# The_Yowler_v9.net
KiCad netlist of a schematic drawn in EAGLE
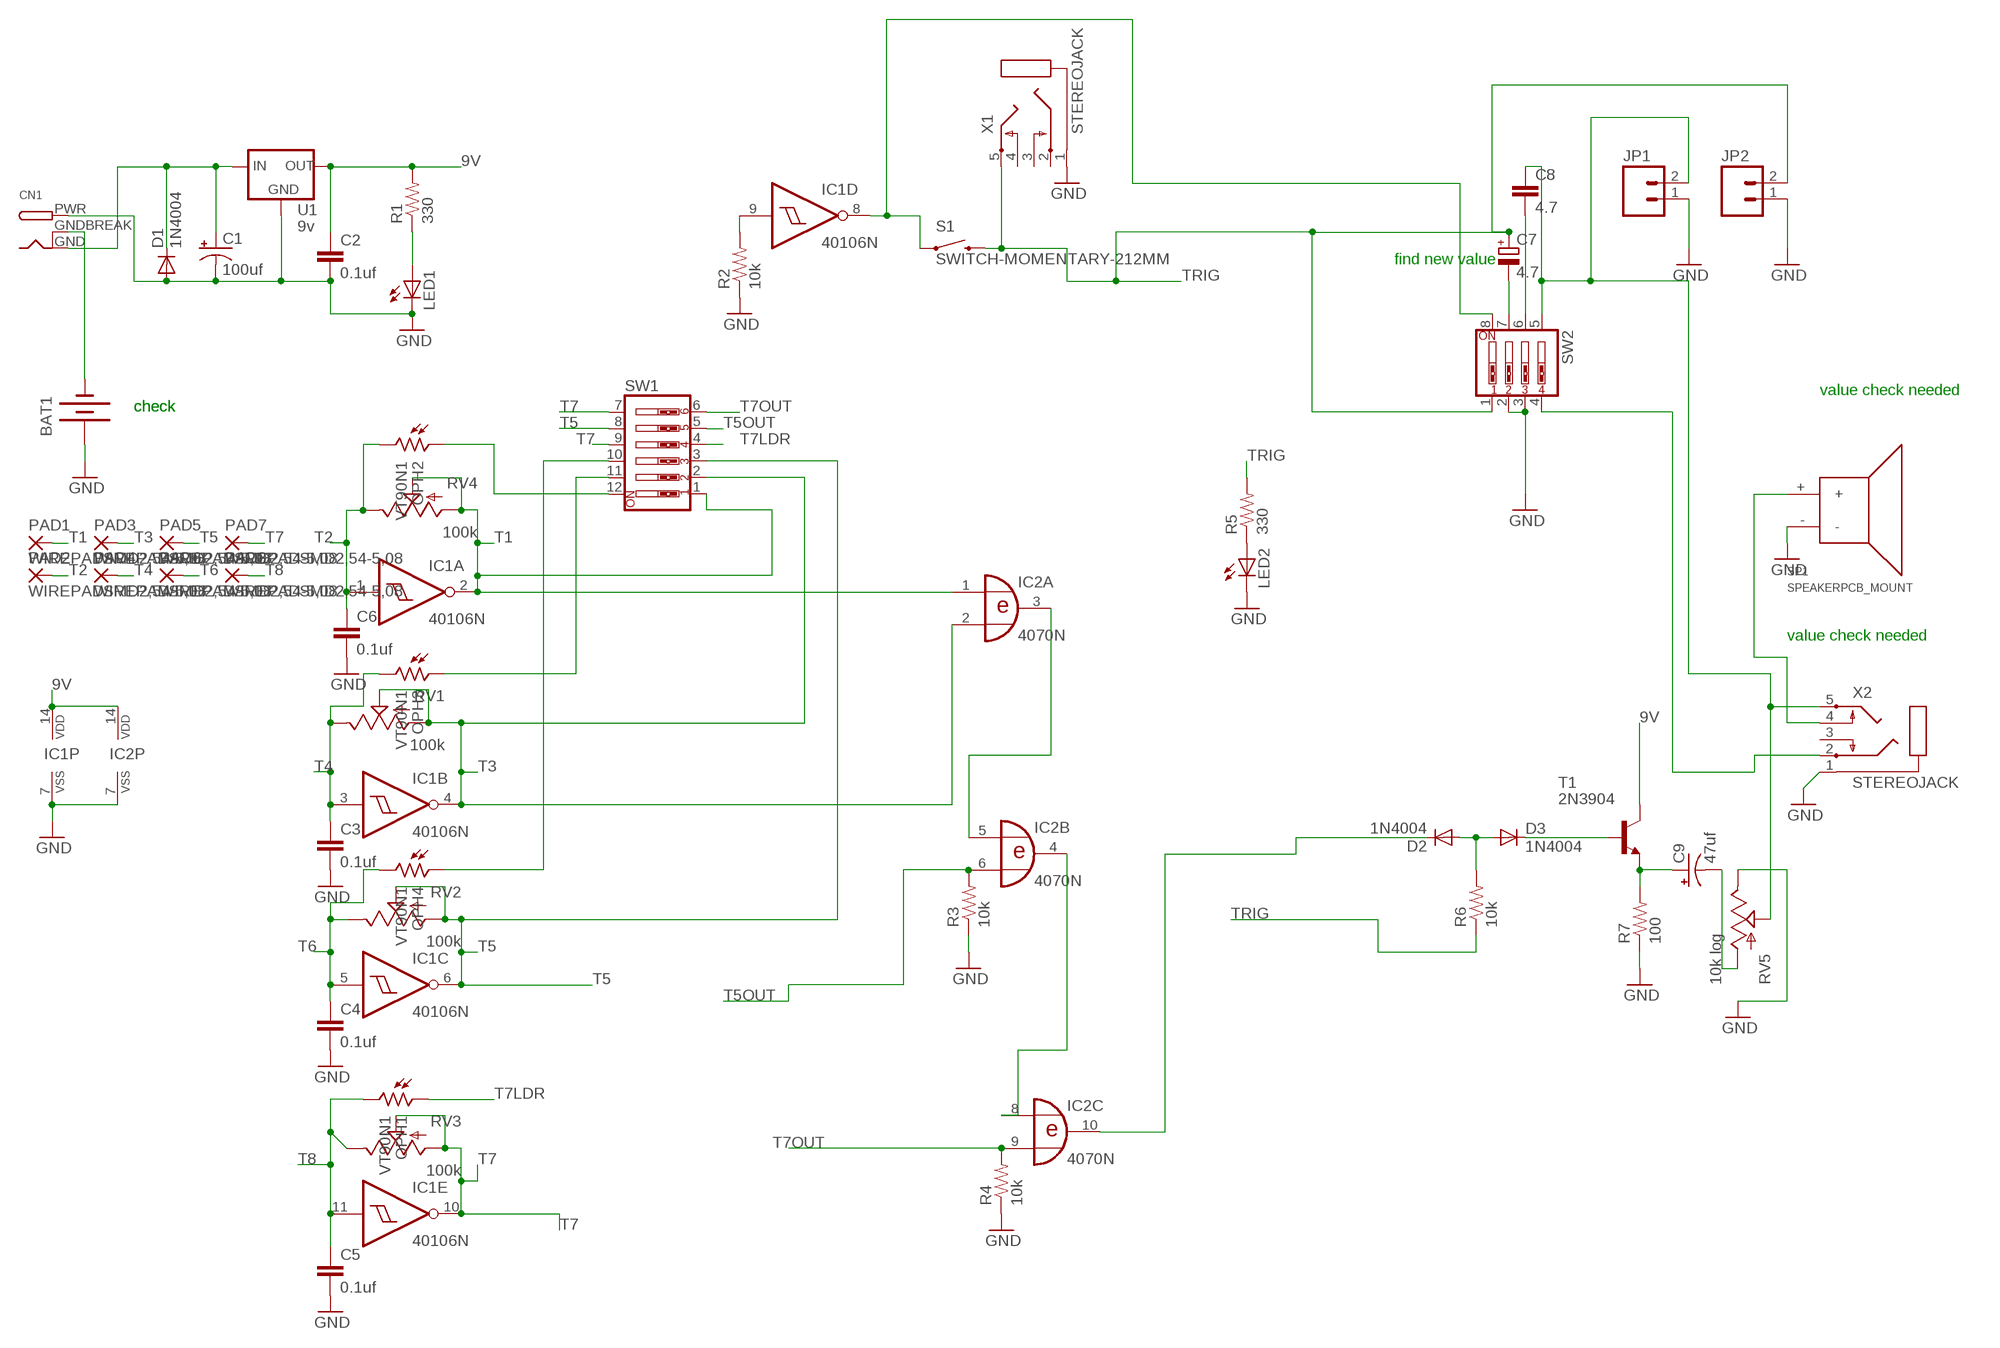
[diagram p0: schematic, sheet 1]

(export (version "E")
  (design (tool "Eeschema 10.0.6"))
  (components
    (comp (ref "BAT1")
      (value "BATTERY9V")
      (footprint "eagle-import:BATTCON_9V")
      (libsource (lib "eagle-import") (part "BATTERY9V"))
    )
    (comp (ref "C1")
      (value "100uf")
      (footprint "eagle-import:E5-6")
      (libsource (lib "eagle-import") (part "CPOL-USE5-6"))
    )
    (comp (ref "C2")
      (value "0.1uf")
      (footprint "eagle-import:CAP-PTH-5MM")
      (libsource (lib "eagle-import") (part "CAPPTH1"))
    )
    (comp (ref "C3")
      (value "0.1uf")
      (footprint "eagle-import:CAP-PTH-5MM")
      (libsource (lib "eagle-import") (part "CAPPTH1"))
    )
    (comp (ref "C4")
      (value "0.1uf")
      (footprint "eagle-import:CAP-PTH-5MM")
      (libsource (lib "eagle-import") (part "CAPPTH1"))
    )
    (comp (ref "C5")
      (value "0.1uf")
      (footprint "eagle-import:CAP-PTH-5MM")
      (libsource (lib "eagle-import") (part "CAPPTH1"))
    )
    (comp (ref "C6")
      (value "0.1uf")
      (footprint "eagle-import:CAP-PTH-5MM")
      (libsource (lib "eagle-import") (part "CAPPTH1"))
    )
    (comp (ref "C7")
      (value "4.7")
      (footprint "eagle-import:E5-5")
      (libsource (lib "eagle-import") (part "CPOL-EUE5-5"))
    )
    (comp (ref "C8")
      (value "4.7")
      (footprint "eagle-import:C050-030X075")
      (libsource (lib "eagle-import") (part "C-EU050-030X075"))
    )
    (comp (ref "C9")
      (value "47uf")
      (footprint "eagle-import:CPOL-RADIAL-10UF-25V")
      (libsource (lib "eagle-import") (part "CAP_POLPTH2"))
    )
    (comp (ref "CN1")
      (value "DCBARRELPTH")
      (footprint "eagle-import:DCJACK_2MM_PTH")
      (libsource (lib "eagle-import") (part "DCBARRELPTH"))
    )
    (comp (ref "D1")
      (value "1N4004")
      (footprint "eagle-import:DO41-10")
      (libsource (lib "eagle-import") (part "1N4004"))
    )
    (comp (ref "D2")
      (value "1N4004")
      (footprint "eagle-import:DO41-10")
      (libsource (lib "eagle-import") (part "1N4004"))
    )
    (comp (ref "D3")
      (value "1N4004")
      (footprint "eagle-import:DO41-10")
      (libsource (lib "eagle-import") (part "1N4004"))
    )
    (comp (ref "IC1")
      (value "40106N")
      (footprint "eagle-import:DIL14")
      (libsource (lib "eagle-import") (part "40106N"))
    )
    (comp (ref "IC2")
      (value "4070N")
      (footprint "eagle-import:DIL14")
      (libsource (lib "eagle-import") (part "4070N"))
    )
    (comp (ref "JP1")
      (value "M02POGO_PIN_HOLES_ONLY")
      (footprint "eagle-import:1X02_PP_HOLES_ONLY")
      (libsource (lib "eagle-import") (part "M02POGO_PIN_HOLES_ONLY"))
    )
    (comp (ref "JP2")
      (value "M02POGO_PIN_HOLES_ONLY")
      (footprint "eagle-import:1X02_PP_HOLES_ONLY")
      (libsource (lib "eagle-import") (part "M02POGO_PIN_HOLES_ONLY"))
    )
    (comp (ref "LED1")
      (value "LED3MM")
      (footprint "eagle-import:LED3MM")
      (libsource (lib "eagle-import") (part "LED3MM"))
    )
    (comp (ref "LED2")
      (value "LED3MM")
      (footprint "eagle-import:LED3MM")
      (libsource (lib "eagle-import") (part "LED3MM"))
    )
    (comp (ref "OPH1")
      (value "VT90N1")
      (footprint "eagle-import:VT900")
      (libsource (lib "eagle-import") (part "VT90N1"))
    )
    (comp (ref "OPH2")
      (value "VT90N1")
      (footprint "eagle-import:VT900")
      (libsource (lib "eagle-import") (part "VT90N1"))
    )
    (comp (ref "OPH3")
      (value "VT90N1")
      (footprint "eagle-import:VT900")
      (libsource (lib "eagle-import") (part "VT90N1"))
    )
    (comp (ref "OPH4")
      (value "VT90N1")
      (footprint "eagle-import:VT900")
      (libsource (lib "eagle-import") (part "VT90N1"))
    )
    (comp (ref "PAD1")
      (value "WIREPADSMD2,54-5,08")
      (footprint "eagle-import:SMD2,54-5,08")
      (libsource (lib "eagle-import") (part "WIREPADSMD2,54-5,08"))
    )
    (comp (ref "PAD2")
      (value "WIREPADSMD2,54-5,08")
      (footprint "eagle-import:SMD2,54-5,08")
      (libsource (lib "eagle-import") (part "WIREPADSMD2,54-5,08"))
    )
    (comp (ref "PAD3")
      (value "WIREPADSMD2,54-5,08")
      (footprint "eagle-import:SMD2,54-5,08")
      (libsource (lib "eagle-import") (part "WIREPADSMD2,54-5,08"))
    )
    (comp (ref "PAD4")
      (value "WIREPADSMD2,54-5,08")
      (footprint "eagle-import:SMD2,54-5,08")
      (libsource (lib "eagle-import") (part "WIREPADSMD2,54-5,08"))
    )
    (comp (ref "PAD5")
      (value "WIREPADSMD2,54-5,08")
      (footprint "eagle-import:SMD2,54-5,08")
      (libsource (lib "eagle-import") (part "WIREPADSMD2,54-5,08"))
    )
    (comp (ref "PAD6")
      (value "WIREPADSMD2,54-5,08")
      (footprint "eagle-import:SMD2,54-5,08")
      (libsource (lib "eagle-import") (part "WIREPADSMD2,54-5,08"))
    )
    (comp (ref "PAD7")
      (value "WIREPADSMD2,54-5,08")
      (footprint "eagle-import:SMD2,54-5,08")
      (libsource (lib "eagle-import") (part "WIREPADSMD2,54-5,08"))
    )
    (comp (ref "PAD8")
      (value "WIREPADSMD2,54-5,08")
      (footprint "eagle-import:SMD2,54-5,08")
      (libsource (lib "eagle-import") (part "WIREPADSMD2,54-5,08"))
    )
    (comp (ref "R1")
      (value "330")
      (footprint "eagle-import:AXIAL-0.4")
      (libsource (lib "eagle-import") (part "RESISTORPTH-1/4W"))
    )
    (comp (ref "R2")
      (value "10k")
      (footprint "eagle-import:AXIAL-0.4")
      (libsource (lib "eagle-import") (part "RESISTORPTH-1/4W"))
    )
    (comp (ref "R3")
      (value "10k")
      (footprint "eagle-import:AXIAL-0.4")
      (libsource (lib "eagle-import") (part "RESISTORPTH-1/4W"))
    )
    (comp (ref "R4")
      (value "10k")
      (footprint "eagle-import:AXIAL-0.4")
      (libsource (lib "eagle-import") (part "RESISTORPTH-1/4W"))
    )
    (comp (ref "R5")
      (value "330")
      (footprint "eagle-import:AXIAL-0.4")
      (libsource (lib "eagle-import") (part "RESISTORPTH-1/4W"))
    )
    (comp (ref "R6")
      (value "10k")
      (footprint "eagle-import:AXIAL-0.4")
      (libsource (lib "eagle-import") (part "RESISTORPTH-1/4W"))
    )
    (comp (ref "R7")
      (value "100")
      (footprint "eagle-import:AXIAL-0.4")
      (libsource (lib "eagle-import") (part "RESISTORPTH-1/4W"))
    )
    (comp (ref "RV1")
      (value "100k")
      (footprint "eagle-import:ALPS_POT")
      (libsource (lib "eagle-import") (part "POT"))
    )
    (comp (ref "RV2")
      (value "100k")
      (footprint "eagle-import:ALPS_POT")
      (libsource (lib "eagle-import") (part "POT"))
    )
    (comp (ref "RV3")
      (value "100k")
      (footprint "eagle-import:ALPS_POT")
      (libsource (lib "eagle-import") (part "POT"))
    )
    (comp (ref "RV4")
      (value "100k")
      (footprint "eagle-import:ALPS_POT")
      (libsource (lib "eagle-import") (part "POT"))
    )
    (comp (ref "RV5")
      (value "10k log")
      (footprint "eagle-import:ALPS_POT")
      (libsource (lib "eagle-import") (part "POT"))
    )
    (comp (ref "S1")
      (value "SWITCH-MOMENTARY-212MM")
      (footprint "eagle-import:TACTILE-PTH-12MM")
      (libsource (lib "eagle-import") (part "SWITCH-MOMENTARY-212MM"))
    )
    (comp (ref "SP1")
      (value "SPEAKERPCB_MOUNT")
      (footprint "eagle-import:PCB_MOUNT_SPEAKER")
      (fields (field (name "MFG") "SANCO"))
      (libsource (lib "eagle-import") (part "SPEAKERPCB_MOUNT"))
    )
    (comp (ref "SW1")
      (value "SW_DIP-6")
      (footprint "eagle-import:EDG-06")
      (libsource (lib "eagle-import") (part "SW_DIP-6"))
    )
    (comp (ref "SW2")
      (value "SW_DIP-4")
      (footprint "eagle-import:EDG-04")
      (libsource (lib "eagle-import") (part "SW_DIP-4"))
    )
    (comp (ref "T1")
      (value "2N3904")
      (footprint "eagle-import:TO92")
      (libsource (lib "eagle-import") (part "2N3904"))
    )
    (comp (ref "U1")
      (value "9v")
      (footprint "eagle-import:TO-220-ALT")
      (libsource (lib "eagle-import") (part "V_REG_78XX-TO-220"))
    )
    (comp (ref "X1")
      (value "STEREOJACK")
      (footprint "eagle-import:STX3100")
      (libsource (lib "eagle-import") (part "STEREOJACK"))
    )
    (comp (ref "X2")
      (value "STEREOJACK")
      (footprint "eagle-import:STX3100")
      (libsource (lib "eagle-import") (part "STEREOJACK"))
    )
  )
  (nets
    (net (code "1") (name "/9V") (class "Default")
      (node (ref "C2") (pin "1") (pinfunction "1_1") (pintype "passive"))
      (node (ref "IC1") (pin "14") (pinfunction "VDD_14") (pintype "power_in"))
      (node (ref "IC2") (pin "14") (pinfunction "VDD_14") (pintype "power_in"))
      (node (ref "R1") (pin "P$2") (pinfunction "2_P$2") (pintype "passive"))
      (node (ref "T1") (pin "1") (pinfunction "C_1") (pintype "passive"))
      (node (ref "U1") (pin "OUT") (pinfunction "OUT_OUT") (pintype "output"))
    )
    (net (code "2") (name "/T1") (class "Default")
      (node (ref "IC1") (pin "2") (pinfunction "O_2") (pintype "output"))
      (node (ref "IC2") (pin "1") (pinfunction "I0_1") (pintype "input"))
      (node (ref "PAD1") (pin "1") (pinfunction "P_1") (pintype "passive"))
      (node (ref "RV4") (pin "P$2") (pinfunction "S_P$2") (pintype "passive"))
      (node (ref "RV4") (pin "P$3") (pinfunction "A_P$3") (pintype "passive"))
      (node (ref "SW1") (pin "1") (pinfunction "1_1") (pintype "passive"))
    )
    (net (code "3") (name "/T2") (class "Default")
      (node (ref "C6") (pin "1") (pinfunction "1_1") (pintype "passive"))
      (node (ref "IC1") (pin "1") (pinfunction "I_1") (pintype "input"))
      (node (ref "OPH2") (pin "2") (pinfunction "2_2") (pintype "passive"))
      (node (ref "PAD2") (pin "1") (pinfunction "P_1") (pintype "passive"))
      (node (ref "RV4") (pin "P$1") (pinfunction "E_P$1") (pintype "passive"))
    )
    (net (code "4") (name "/T3") (class "Default")
      (node (ref "IC1") (pin "4") (pinfunction "O_4") (pintype "output"))
      (node (ref "IC2") (pin "2") (pinfunction "I1_2") (pintype "input"))
      (node (ref "PAD3") (pin "1") (pinfunction "P_1") (pintype "passive"))
      (node (ref "RV1") (pin "P$2") (pinfunction "S_P$2") (pintype "passive"))
      (node (ref "RV1") (pin "P$3") (pinfunction "A_P$3") (pintype "passive"))
      (node (ref "SW1") (pin "2") (pinfunction "2_2") (pintype "passive"))
    )
    (net (code "5") (name "/T4") (class "Default")
      (node (ref "C3") (pin "1") (pinfunction "1_1") (pintype "passive"))
      (node (ref "IC1") (pin "3") (pinfunction "I_3") (pintype "input"))
      (node (ref "OPH3") (pin "2") (pinfunction "2_2") (pintype "passive"))
      (node (ref "PAD4") (pin "1") (pinfunction "P_1") (pintype "passive"))
      (node (ref "RV1") (pin "P$1") (pinfunction "E_P$1") (pintype "passive"))
    )
    (net (code "6") (name "/T5") (class "Default")
      (node (ref "IC1") (pin "6") (pinfunction "O_6") (pintype "output"))
      (node (ref "PAD5") (pin "1") (pinfunction "P_1") (pintype "passive"))
      (node (ref "RV2") (pin "P$2") (pinfunction "S_P$2") (pintype "passive"))
      (node (ref "RV2") (pin "P$3") (pinfunction "A_P$3") (pintype "passive"))
      (node (ref "SW1") (pin "3") (pinfunction "3_3") (pintype "passive"))
      (node (ref "SW1") (pin "8") (pinfunction "8_8") (pintype "passive"))
    )
    (net (code "7") (name "/T5OUT") (class "Default")
      (node (ref "IC2") (pin "6") (pinfunction "I1_6") (pintype "input"))
      (node (ref "R3") (pin "P$2") (pinfunction "2_P$2") (pintype "passive"))
      (node (ref "SW1") (pin "5") (pinfunction "5_5") (pintype "passive"))
    )
    (net (code "8") (name "/T6") (class "Default")
      (node (ref "C4") (pin "1") (pinfunction "1_1") (pintype "passive"))
      (node (ref "IC1") (pin "5") (pinfunction "I_5") (pintype "input"))
      (node (ref "OPH4") (pin "2") (pinfunction "2_2") (pintype "passive"))
      (node (ref "PAD6") (pin "1") (pinfunction "P_1") (pintype "passive"))
      (node (ref "RV2") (pin "P$1") (pinfunction "E_P$1") (pintype "passive"))
    )
    (net (code "9") (name "/T7") (class "Default")
      (node (ref "IC1") (pin "10") (pinfunction "O_10") (pintype "output"))
      (node (ref "PAD7") (pin "1") (pinfunction "P_1") (pintype "passive"))
      (node (ref "RV3") (pin "P$2") (pinfunction "S_P$2") (pintype "passive"))
      (node (ref "RV3") (pin "P$3") (pinfunction "A_P$3") (pintype "passive"))
      (node (ref "SW1") (pin "7") (pinfunction "7_7") (pintype "passive"))
      (node (ref "SW1") (pin "9") (pinfunction "9_9") (pintype "passive"))
    )
    (net (code "10") (name "/T7LDR") (class "Default")
      (node (ref "OPH1") (pin "1") (pinfunction "1_1") (pintype "passive"))
      (node (ref "SW1") (pin "4") (pinfunction "4_4") (pintype "passive"))
    )
    (net (code "11") (name "/T7OUT") (class "Default")
      (node (ref "IC2") (pin "9") (pinfunction "I1_9") (pintype "input"))
      (node (ref "R4") (pin "P$2") (pinfunction "2_P$2") (pintype "passive"))
      (node (ref "SW1") (pin "6") (pinfunction "6_6") (pintype "passive"))
    )
    (net (code "12") (name "/T8") (class "Default")
      (node (ref "C5") (pin "1") (pinfunction "1_1") (pintype "passive"))
      (node (ref "IC1") (pin "11") (pinfunction "I_11") (pintype "input"))
      (node (ref "OPH1") (pin "2") (pinfunction "2_2") (pintype "passive"))
      (node (ref "PAD8") (pin "1") (pinfunction "P_1") (pintype "passive"))
      (node (ref "RV3") (pin "P$1") (pinfunction "E_P$1") (pintype "passive"))
    )
    (net (code "13") (name "/TRIG") (class "Default")
      (node (ref "C7") (pin "+") (pinfunction "+_+") (pintype "passive"))
      (node (ref "JP2") (pin "2") (pinfunction "2_2") (pintype "passive"))
      (node (ref "R5") (pin "P$2") (pinfunction "2_P$2") (pintype "passive"))
      (node (ref "R6") (pin "P$1") (pinfunction "1_P$1") (pintype "passive"))
      (node (ref "S1") (pin "3") (pinfunction "2_3") (pintype "passive"))
      (node (ref "SW2") (pin "1") (pinfunction "1_1") (pintype "passive"))
      (node (ref "X1") (pin "5") (pinfunction "5_5") (pintype "passive"))
    )
    (net (code "14") (name "GND") (class "Default")
      (node (ref "BAT1") (pin "+") (pinfunction "+_+") (pintype "power_in"))
      (node (ref "C1") (pin "-") (pinfunction "-_-") (pintype "passive"))
      (node (ref "C2") (pin "2") (pinfunction "2_2") (pintype "passive"))
      (node (ref "C3") (pin "2") (pinfunction "2_2") (pintype "passive"))
      (node (ref "C4") (pin "2") (pinfunction "2_2") (pintype "passive"))
      (node (ref "C5") (pin "2") (pinfunction "2_2") (pintype "passive"))
      (node (ref "C6") (pin "2") (pinfunction "2_2") (pintype "passive"))
      (node (ref "CN1") (pin "PWR") (pinfunction "PWR_PWR") (pintype "power_in"))
      (node (ref "D1") (pin "A") (pinfunction "A_A") (pintype "passive"))
      (node (ref "IC1") (pin "7") (pinfunction "VSS_7") (pintype "power_in"))
      (node (ref "IC2") (pin "7") (pinfunction "VSS_7") (pintype "power_in"))
      (node (ref "JP1") (pin "1") (pinfunction "1_1") (pintype "passive"))
      (node (ref "JP2") (pin "1") (pinfunction "1_1") (pintype "passive"))
      (node (ref "LED1") (pin "K") (pinfunction "C_K") (pintype "passive"))
      (node (ref "LED2") (pin "K") (pinfunction "C_K") (pintype "passive"))
      (node (ref "R2") (pin "P$1") (pinfunction "1_P$1") (pintype "passive"))
      (node (ref "R3") (pin "P$1") (pinfunction "1_P$1") (pintype "passive"))
      (node (ref "R4") (pin "P$1") (pinfunction "1_P$1") (pintype "passive"))
      (node (ref "R7") (pin "P$1") (pinfunction "1_P$1") (pintype "passive"))
      (node (ref "RV5") (pin "P$1") (pinfunction "E_P$1") (pintype "passive"))
      (node (ref "SP1") (pin "-") (pinfunction "-_-") (pintype "bidirectional"))
      (node (ref "SW2") (pin "2") (pinfunction "2_2") (pintype "passive"))
      (node (ref "SW2") (pin "3") (pinfunction "3_3") (pintype "passive"))
      (node (ref "U1") (pin "GND") (pinfunction "GND_GND") (pintype "input"))
      (node (ref "X1") (pin "1") (pinfunction "1_1") (pintype "passive"))
      (node (ref "X2") (pin "1") (pinfunction "1_1") (pintype "passive"))
    )
    (net (code "15") (name "Net-(BAT1-Pad-)") (class "Default")
      (node (ref "BAT1") (pin "-") (pinfunction "-_-") (pintype "power_in"))
      (node (ref "CN1") (pin "GNDBREAK") (pinfunction "GNDBREAK_GNDBREAK") (pintype "power_in"))
    )
    (net (code "16") (name "Net-(C1-Pad+)") (class "Default")
      (node (ref "C1") (pin "+") (pinfunction "+_+") (pintype "passive"))
      (node (ref "CN1") (pin "GND") (pinfunction "GND_GND") (pintype "power_in"))
      (node (ref "D1") (pin "C") (pinfunction "C_C") (pintype "passive"))
      (node (ref "U1") (pin "IN") (pinfunction "IN_IN") (pintype "input"))
    )
    (net (code "17") (name "Net-(C7-Pad-)") (class "Default")
      (node (ref "C7") (pin "-") (pinfunction "-_-") (pintype "passive"))
      (node (ref "SW2") (pin "7") (pinfunction "7_7") (pintype "passive"))
    )
    (net (code "18") (name "Net-(C8-Pad2)") (class "Default")
      (node (ref "C8") (pin "2") (pinfunction "2_2") (pintype "passive"))
      (node (ref "SW2") (pin "6") (pinfunction "6_6") (pintype "passive"))
    )
    (net (code "19") (name "Net-(C9-+)") (class "Default")
      (node (ref "C9") (pin "1") (pinfunction "+_1") (pintype "passive"))
      (node (ref "R7") (pin "P$2") (pinfunction "2_P$2") (pintype "passive"))
      (node (ref "T1") (pin "3") (pinfunction "E_3") (pintype "passive"))
    )
    (net (code "20") (name "Net-(C9--)") (class "Default")
      (node (ref "C9") (pin "2") (pinfunction "-_2") (pintype "passive"))
      (node (ref "RV5") (pin "P$3") (pinfunction "A_P$3") (pintype "passive"))
    )
    (net (code "21") (name "Net-(IC1D-I)") (class "Default")
      (node (ref "IC1") (pin "9") (pinfunction "I_9") (pintype "input"))
      (node (ref "R2") (pin "P$2") (pinfunction "2_P$2") (pintype "passive"))
    )
    (net (code "22") (name "Net-(IC1D-O)") (class "Default")
      (node (ref "IC1") (pin "8") (pinfunction "O_8") (pintype "output"))
      (node (ref "S1") (pin "1") (pinfunction "1_1") (pintype "passive"))
      (node (ref "SW2") (pin "8") (pinfunction "8_8") (pintype "passive"))
    )
    (net (code "23") (name "Net-(IC2A-O)") (class "Default")
      (node (ref "IC2") (pin "3") (pinfunction "O_3") (pintype "output"))
      (node (ref "IC2") (pin "5") (pinfunction "I0_5") (pintype "input"))
    )
    (net (code "24") (name "Net-(IC2B-O)") (class "Default")
      (node (ref "IC2") (pin "4") (pinfunction "O_4") (pintype "output"))
      (node (ref "IC2") (pin "8") (pinfunction "I0_8") (pintype "input"))
    )
    (net (code "25") (name "Net-(IC2C-O)") (class "Default")
      (node (ref "D2") (pin "C") (pinfunction "C_C") (pintype "passive"))
      (node (ref "IC2") (pin "10") (pinfunction "O_10") (pintype "output"))
    )
    (net (code "26") (name "Net-(OPH2-Pad1)") (class "Default")
      (node (ref "OPH2") (pin "1") (pinfunction "1_1") (pintype "passive"))
      (node (ref "SW1") (pin "12") (pinfunction "12_12") (pintype "passive"))
    )
    (net (code "27") (name "Net-(OPH3-Pad1)") (class "Default")
      (node (ref "OPH3") (pin "1") (pinfunction "1_1") (pintype "passive"))
      (node (ref "SW1") (pin "11") (pinfunction "11_11") (pintype "passive"))
    )
    (net (code "28") (name "Net-(OPH4-Pad1)") (class "Default")
      (node (ref "OPH4") (pin "1") (pinfunction "1_1") (pintype "passive"))
      (node (ref "SW1") (pin "10") (pinfunction "10_10") (pintype "passive"))
    )
    (net (code "29") (name "Net-(R1-1)") (class "Default")
      (node (ref "LED1") (pin "A") (pinfunction "A_A") (pintype "passive"))
      (node (ref "R1") (pin "P$1") (pinfunction "1_P$1") (pintype "passive"))
    )
    (net (code "30") (name "Net-(R5-1)") (class "Default")
      (node (ref "LED2") (pin "A") (pinfunction "A_A") (pintype "passive"))
      (node (ref "R5") (pin "P$1") (pinfunction "1_P$1") (pintype "passive"))
    )
    (net (code "31") (name "Net-(R6-2)") (class "Default")
      (node (ref "D2") (pin "A") (pinfunction "A_A") (pintype "passive"))
      (node (ref "D3") (pin "A") (pinfunction "A_A") (pintype "passive"))
      (node (ref "R6") (pin "P$2") (pinfunction "2_P$2") (pintype "passive"))
    )
    (net (code "32") (name "Net-(RV5-S)") (class "Default")
      (node (ref "C8") (pin "1") (pinfunction "1_1") (pintype "passive"))
      (node (ref "JP1") (pin "2") (pinfunction "2_2") (pintype "passive"))
      (node (ref "RV5") (pin "P$2") (pinfunction "S_P$2") (pintype "passive"))
      (node (ref "SW2") (pin "5") (pinfunction "5_5") (pintype "passive"))
      (node (ref "X2") (pin "5") (pinfunction "5_5") (pintype "passive"))
    )
    (net (code "33") (name "Net-(SP1-Pad+)") (class "Default")
      (node (ref "SP1") (pin "+") (pinfunction "+_+") (pintype "bidirectional"))
      (node (ref "X2") (pin "4") (pinfunction "4_4") (pintype "passive"))
    )
    (net (code "34") (name "Net-(SW2-Pad4)") (class "Default")
      (node (ref "SW2") (pin "4") (pinfunction "4_4") (pintype "passive"))
      (node (ref "X2") (pin "2") (pinfunction "2_2") (pintype "passive"))
    )
    (net (code "35") (name "Net-(T1-B)") (class "Default")
      (node (ref "D3") (pin "C") (pinfunction "C_C") (pintype "passive"))
      (node (ref "T1") (pin "2") (pinfunction "B_2") (pintype "passive"))
    )
    (net (code "36") (name "unconnected-(X1-Pad2)") (class "Default")
      (node (ref "X1") (pin "2") (pinfunction "2_2") (pintype "passive"))
    )
    (net (code "37") (name "unconnected-(X1-Pad3)") (class "Default")
      (node (ref "X1") (pin "3") (pinfunction "3_3") (pintype "passive"))
    )
    (net (code "38") (name "unconnected-(X1-Pad4)") (class "Default")
      (node (ref "X1") (pin "4") (pinfunction "4_4") (pintype "passive"))
    )
    (net (code "39") (name "unconnected-(X2-Pad3)") (class "Default")
      (node (ref "X2") (pin "3") (pinfunction "3_3") (pintype "passive"))
    )
  )
)
